# TangPrimer_base.net
KiCad netlist of a schematic drawn in EAGLE
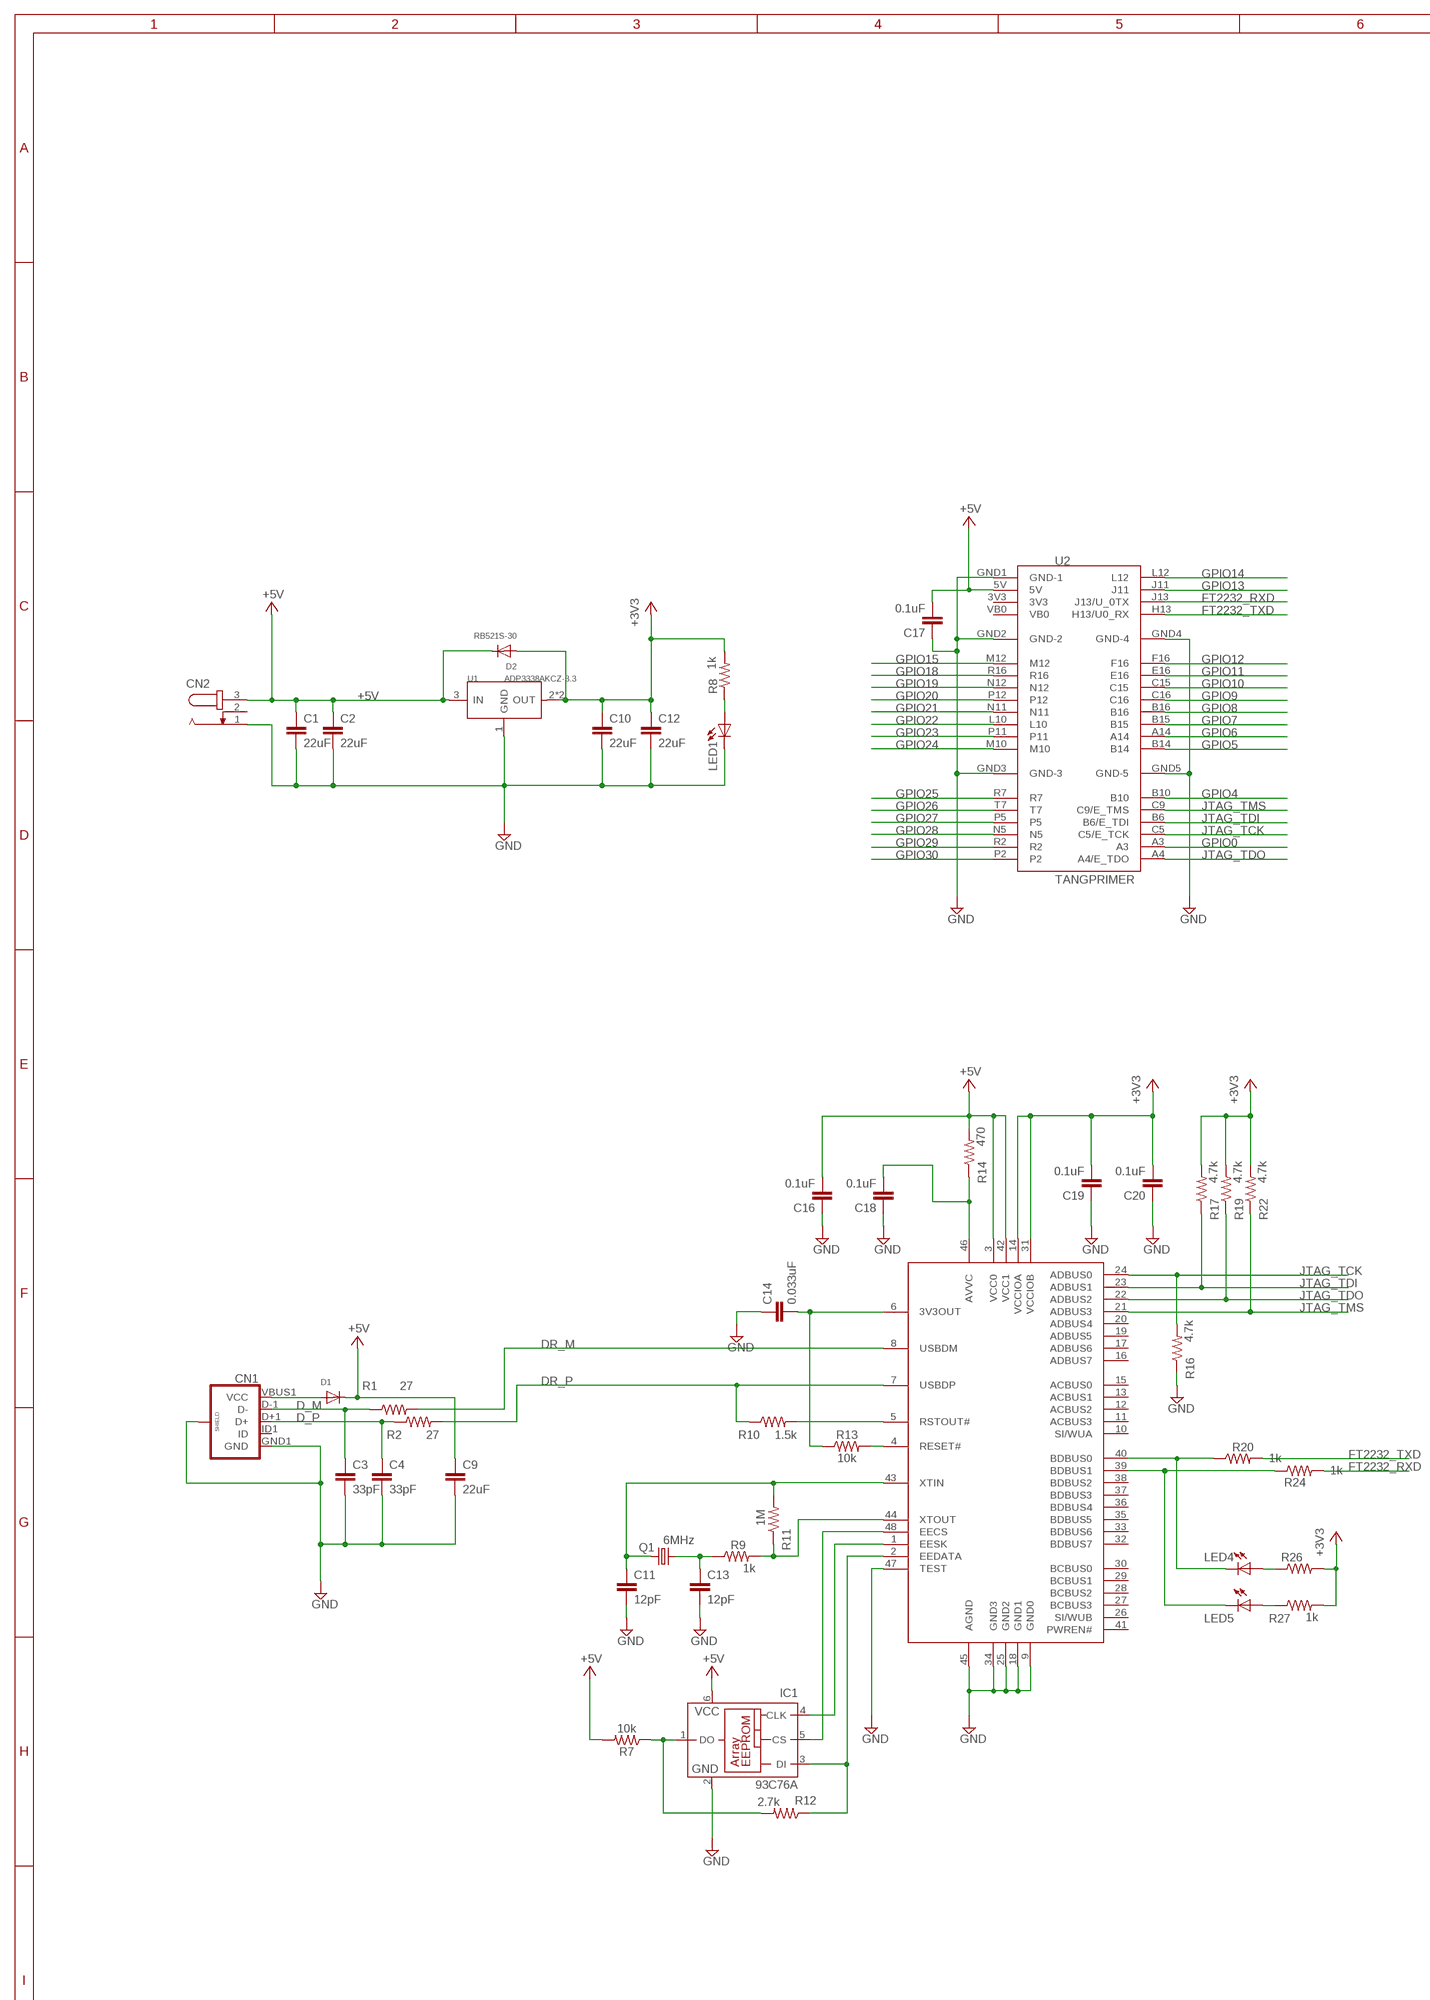
[diagram p0: schematic, sheet 1, part 1 of 2]
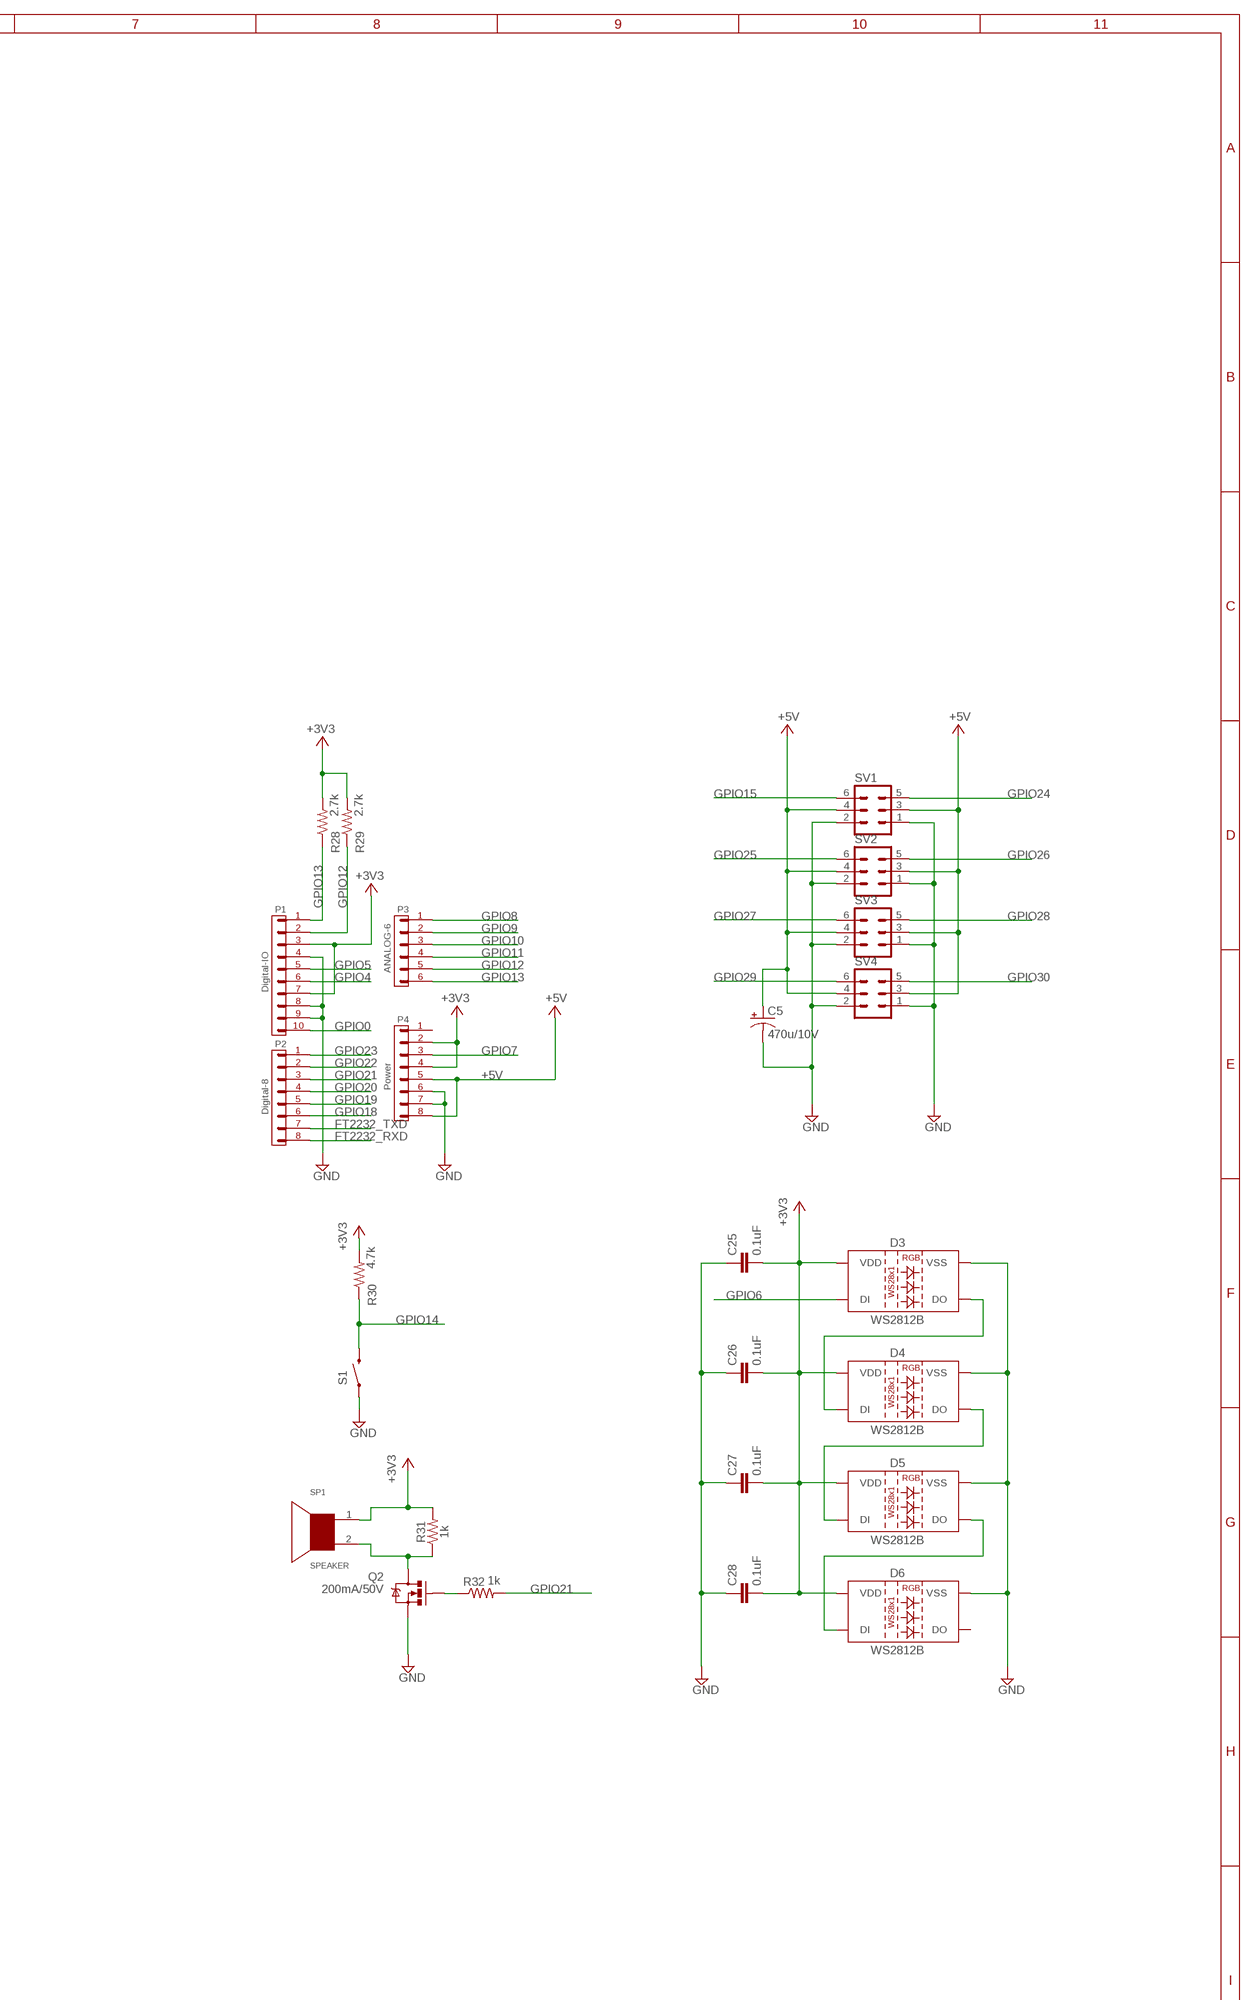
[diagram p1: schematic, sheet 1, part 2 of 2]

(export (version "E")
  (design (tool "Eeschema 10.0.6"))
  (components
    (comp (ref "C1")
      (value "22uF")
      (footprint "eagle-import:0603")
      (libsource (lib "eagle-import") (part "10UF-0603-6.3V-20%"))
    )
    (comp (ref "C2")
      (value "22uF")
      (footprint "eagle-import:0603")
      (libsource (lib "eagle-import") (part "10UF-0603-6.3V-20%"))
    )
    (comp (ref "C3")
      (value "33pF")
      (footprint "eagle-import:0603")
      (libsource (lib "eagle-import") (part "47PF-0603-50V-5%"))
    )
    (comp (ref "C4")
      (value "33pF")
      (footprint "eagle-import:0603")
      (libsource (lib "eagle-import") (part "47PF-0603-50V-5%"))
    )
    (comp (ref "C5")
      (value "470u/10V")
      (footprint "eagle-import:E2,5-7")
      (libsource (lib "eagle-import") (part "CPOL-USE2.5-7"))
    )
    (comp (ref "C9")
      (value "22uF")
      (footprint "eagle-import:0603")
      (libsource (lib "eagle-import") (part "10UF-0603-6.3V-20%"))
    )
    (comp (ref "C10")
      (value "22uF")
      (footprint "eagle-import:0603")
      (libsource (lib "eagle-import") (part "10UF-0603-6.3V-20%"))
    )
    (comp (ref "C11")
      (value "12pF")
      (footprint "eagle-import:0603")
      (libsource (lib "eagle-import") (part "47PF-0603-50V-5%"))
    )
    (comp (ref "C12")
      (value "22uF")
      (footprint "eagle-import:0603")
      (libsource (lib "eagle-import") (part "10UF-0603-6.3V-20%"))
    )
    (comp (ref "C13")
      (value "12pF")
      (footprint "eagle-import:0603")
      (libsource (lib "eagle-import") (part "47PF-0603-50V-5%"))
    )
    (comp (ref "C14")
      (value "0.033uF")
      (footprint "eagle-import:0603")
      (libsource (lib "eagle-import") (part "47PF-0603-50V-5%"))
    )
    (comp (ref "C16")
      (value "0.1uF")
      (footprint "eagle-import:0603")
      (libsource (lib "eagle-import") (part "0.1UF-0603-25V-5%"))
    )
    (comp (ref "C17")
      (value "0.1uF")
      (footprint "eagle-import:0603")
      (libsource (lib "eagle-import") (part "0.1UF-0603-25V-5%"))
    )
    (comp (ref "C18")
      (value "0.1uF")
      (footprint "eagle-import:0603")
      (libsource (lib "eagle-import") (part "0.1UF-0603-25V-5%"))
    )
    (comp (ref "C19")
      (value "0.1uF")
      (footprint "eagle-import:0603")
      (libsource (lib "eagle-import") (part "0.1UF-0603-25V-5%"))
    )
    (comp (ref "C20")
      (value "0.1uF")
      (footprint "eagle-import:0603")
      (libsource (lib "eagle-import") (part "0.1UF-0603-25V-5%"))
    )
    (comp (ref "C25")
      (value "0.1uF")
      (footprint "eagle-import:0603")
      (libsource (lib "eagle-import") (part "0.1UF-0603-25V-5%"))
    )
    (comp (ref "C26")
      (value "0.1uF")
      (footprint "eagle-import:0603")
      (libsource (lib "eagle-import") (part "0.1UF-0603-25V-5%"))
    )
    (comp (ref "C27")
      (value "0.1uF")
      (footprint "eagle-import:0603")
      (libsource (lib "eagle-import") (part "0.1UF-0603-25V-5%"))
    )
    (comp (ref "C28")
      (value "0.1uF")
      (footprint "eagle-import:0603")
      (libsource (lib "eagle-import") (part "0.1UF-0603-25V-5%"))
    )
    (comp (ref "CN1")
      (value "MCUBF-09")
      (footprint "eagle-import:MCUBF-09")
      (libsource (lib "eagle-import") (part "MCUBF-09"))
    )
    (comp (ref "CN2")
      (value "JACK-PLUG0")
      (footprint "eagle-import:SPC4077")
      (libsource (lib "eagle-import") (part "JACK-PLUG0"))
    )
    (comp (ref "D1")
      (value "DIODE_SOD-123FL")
      (footprint "eagle-import:SOD-123FL")
      (libsource (lib "eagle-import") (part "DIODE_SOD-123FL"))
    )
    (comp (ref "D2")
      (value "RB521S-30")
      (footprint "eagle-import:SOD-523")
      (libsource (lib "eagle-import") (part "DIODESOD-523"))
    )
    (comp (ref "D3")
      (value "WS2812B")
      (footprint "eagle-import:WS2812_2020")
      (libsource (lib "eagle-import") (part "WS2812_2020"))
    )
    (comp (ref "D4")
      (value "WS2812B")
      (footprint "eagle-import:WS2812_2020")
      (libsource (lib "eagle-import") (part "WS2812_2020"))
    )
    (comp (ref "D5")
      (value "WS2812B")
      (footprint "eagle-import:WS2812_2020")
      (libsource (lib "eagle-import") (part "WS2812_2020"))
    )
    (comp (ref "D6")
      (value "WS2812B")
      (footprint "eagle-import:WS2812_2020")
      (libsource (lib "eagle-import") (part "WS2812_2020"))
    )
    (comp (ref "IC1")
      (value "93C76A")
      (footprint "eagle-import:SOT23-6")
      (libsource (lib "eagle-import") (part "9376?AC"))
    )
    (comp (ref "IC2")
      (value "FT2232L")
      (footprint "eagle-import:LQFP48")
      (libsource (lib "eagle-import") (part "FT2232L"))
    )
    (comp (ref "LED1")
      (value "LEDCHIP-LED0805")
      (footprint "eagle-import:CHIP-LED0805")
      (libsource (lib "eagle-import") (part "LEDCHIP-LED0805"))
    )
    (comp (ref "LED4")
      (value "LEDCHIP-LED0805")
      (footprint "eagle-import:CHIP-LED0805")
      (libsource (lib "eagle-import") (part "LEDCHIP-LED0805"))
    )
    (comp (ref "LED5")
      (value "LEDCHIP-LED0805")
      (footprint "eagle-import:CHIP-LED0805")
      (libsource (lib "eagle-import") (part "LEDCHIP-LED0805"))
    )
    (comp (ref "Q1")
      (value "6MHz")
      (footprint "eagle-import:SM49")
      (libsource (lib "eagle-import") (part "CRYSTALSM49"))
    )
    (comp (ref "Q2")
      (value "200mA/50V")
      (footprint "eagle-import:SOT23-3")
      (libsource (lib "eagle-import") (part "MOSFET-NCHANNELBSS138"))
    )
    (comp (ref "R1")
      (value "27")
      (footprint "eagle-import:0603")
      (libsource (lib "eagle-import") (part "RESISTOR0603"))
    )
    (comp (ref "R2")
      (value "27")
      (footprint "eagle-import:0603")
      (libsource (lib "eagle-import") (part "RESISTOR0603"))
    )
    (comp (ref "R7")
      (value "10k")
      (footprint "eagle-import:0603")
      (libsource (lib "eagle-import") (part "RESISTOR0603"))
    )
    (comp (ref "R8")
      (value "1k")
      (footprint "eagle-import:0603")
      (libsource (lib "eagle-import") (part "RESISTOR0603"))
    )
    (comp (ref "R9")
      (value "1k")
      (footprint "eagle-import:0603")
      (libsource (lib "eagle-import") (part "RESISTOR0603"))
    )
    (comp (ref "R10")
      (value "1.5k")
      (footprint "eagle-import:0603")
      (libsource (lib "eagle-import") (part "RESISTOR0603"))
    )
    (comp (ref "R11")
      (value "1M")
      (footprint "eagle-import:0603")
      (libsource (lib "eagle-import") (part "RESISTOR0603"))
    )
    (comp (ref "R12")
      (value "2.7k")
      (footprint "eagle-import:0603")
      (libsource (lib "eagle-import") (part "RESISTOR0603"))
    )
    (comp (ref "R13")
      (value "10k")
      (footprint "eagle-import:0603")
      (libsource (lib "eagle-import") (part "RESISTOR0603"))
    )
    (comp (ref "R14")
      (value "470")
      (footprint "eagle-import:0603")
      (libsource (lib "eagle-import") (part "RESISTOR0603"))
    )
    (comp (ref "R16")
      (value "4.7k")
      (footprint "eagle-import:0603")
      (libsource (lib "eagle-import") (part "RESISTOR0603"))
    )
    (comp (ref "R17")
      (value "4.7k")
      (footprint "eagle-import:0603")
      (libsource (lib "eagle-import") (part "RESISTOR0603"))
    )
    (comp (ref "R19")
      (value "4.7k")
      (footprint "eagle-import:0603")
      (libsource (lib "eagle-import") (part "RESISTOR0603"))
    )
    (comp (ref "R20")
      (value "1k")
      (footprint "eagle-import:0603")
      (libsource (lib "eagle-import") (part "RESISTOR0603"))
    )
    (comp (ref "R22")
      (value "4.7k")
      (footprint "eagle-import:0603")
      (libsource (lib "eagle-import") (part "RESISTOR0603"))
    )
    (comp (ref "R24")
      (value "1k")
      (footprint "eagle-import:0603")
      (libsource (lib "eagle-import") (part "RESISTOR0603"))
    )
    (comp (ref "R26")
      (value "1k")
      (footprint "eagle-import:0603")
      (libsource (lib "eagle-import") (part "RESISTOR0603"))
    )
    (comp (ref "R27")
      (value "1k")
      (footprint "eagle-import:0603")
      (libsource (lib "eagle-import") (part "RESISTOR0603"))
    )
    (comp (ref "R28")
      (value "2.7k")
      (footprint "eagle-import:0603")
      (libsource (lib "eagle-import") (part "RESISTOR0603"))
    )
    (comp (ref "R29")
      (value "2.7k")
      (footprint "eagle-import:0603")
      (libsource (lib "eagle-import") (part "RESISTOR0603"))
    )
    (comp (ref "R30")
      (value "4.7k")
      (footprint "eagle-import:0603")
      (libsource (lib "eagle-import") (part "RESISTOR0603"))
    )
    (comp (ref "R31")
      (value "1k")
      (footprint "eagle-import:0603")
      (libsource (lib "eagle-import") (part "RESISTOR0603"))
    )
    (comp (ref "R32")
      (value "1k")
      (footprint "eagle-import:0603")
      (libsource (lib "eagle-import") (part "RESISTOR0603"))
    )
    (comp (ref "S1")
      (value "SWITCH-MOMENTARY-2SMD-1101NE")
      (footprint "eagle-import:TACTILE-SWITCH-1101NE")
      (libsource (lib "eagle-import") (part "SWITCH-MOMENTARY-2SMD-1101NE"))
    )
    (comp (ref "S2")
      (value "TANGPRIMER_BASE")
      (footprint "eagle-import:TANGPRIMER_BASE")
      (libsource (lib "eagle-import") (part "TANGPRIMER_BASE"))
    )
    (comp (ref "SP1")
      (value "SPEAKER")
      (footprint "eagle-import:SPEAKER")
      (libsource (lib "eagle-import") (part "SPEAKER"))
    )
    (comp (ref "SV1")
      (value "MA03-2")
      (footprint "eagle-import:MA03-2")
      (libsource (lib "eagle-import") (part "MA03-2"))
    )
    (comp (ref "SV2")
      (value "MA03-2")
      (footprint "eagle-import:MA03-2")
      (libsource (lib "eagle-import") (part "MA03-2"))
    )
    (comp (ref "SV3")
      (value "MA03-2")
      (footprint "eagle-import:MA03-2")
      (libsource (lib "eagle-import") (part "MA03-2"))
    )
    (comp (ref "SV4")
      (value "MA03-2")
      (footprint "eagle-import:MA03-2")
      (libsource (lib "eagle-import") (part "MA03-2"))
    )
    (comp (ref "U1")
      (value "ADP3338AKCZ-3.3")
      (footprint "eagle-import:SOT-223")
      (fields (field (name "MPN") "CJT1117-3.3"))
      (libsource (lib "eagle-import") (part "PMIC-CJT1117-3.3(SOT223)"))
    )
    (comp (ref "U2")
      (value "TANGPRIMER")
      (footprint "eagle-import:TANGPRIMER")
      (libsource (lib "eagle-import") (part "TANGPRIMER"))
    )
  )
  (nets
    (net (code "1") (name "+3V3") (class "Default")
      (node (ref "C10") (pin "1") (pinfunction "1_1") (pintype "passive"))
      (node (ref "C12") (pin "1") (pinfunction "1_1") (pintype "passive"))
      (node (ref "C19") (pin "2") (pinfunction "2_2") (pintype "passive"))
      (node (ref "C20") (pin "2") (pinfunction "2_2") (pintype "passive"))
      (node (ref "C25") (pin "2") (pinfunction "2_2") (pintype "passive"))
      (node (ref "C26") (pin "2") (pinfunction "2_2") (pintype "passive"))
      (node (ref "C27") (pin "2") (pinfunction "2_2") (pintype "passive"))
      (node (ref "C28") (pin "2") (pinfunction "2_2") (pintype "passive"))
      (node (ref "D2") (pin "A") (pinfunction "A_A") (pintype "passive"))
      (node (ref "D3") (pin "4") (pinfunction "VDD_4") (pintype "bidirectional"))
      (node (ref "D4") (pin "4") (pinfunction "VDD_4") (pintype "bidirectional"))
      (node (ref "D5") (pin "4") (pinfunction "VDD_4") (pintype "bidirectional"))
      (node (ref "D6") (pin "4") (pinfunction "VDD_4") (pintype "bidirectional"))
      (node (ref "IC2") (pin "14") (pinfunction "VCCIOA_14") (pintype "bidirectional"))
      (node (ref "IC2") (pin "31") (pinfunction "VCCIOB_31") (pintype "bidirectional"))
      (node (ref "R17") (pin "2") (pinfunction "2_2") (pintype "passive"))
      (node (ref "R19") (pin "2") (pinfunction "2_2") (pintype "passive"))
      (node (ref "R22") (pin "2") (pinfunction "2_2") (pintype "passive"))
      (node (ref "R26") (pin "2") (pinfunction "2_2") (pintype "passive"))
      (node (ref "R27") (pin "2") (pinfunction "2_2") (pintype "passive"))
      (node (ref "R28") (pin "2") (pinfunction "2_2") (pintype "passive"))
      (node (ref "R29") (pin "2") (pinfunction "2_2") (pintype "passive"))
      (node (ref "R30") (pin "2") (pinfunction "2_2") (pintype "passive"))
      (node (ref "R31") (pin "2") (pinfunction "2_2") (pintype "passive"))
      (node (ref "R8") (pin "2") (pinfunction "2_2") (pintype "passive"))
      (node (ref "S2") (pin "3V3-1") (pinfunction "3V3-1_3V3-1") (pintype "bidirectional"))
      (node (ref "S2") (pin "3V3-2") (pinfunction "3V3-2_3V3-2") (pintype "bidirectional"))
      (node (ref "S2") (pin "AREF") (pinfunction "AREF_AREF") (pintype "bidirectional"))
      (node (ref "S2") (pin "D11") (pinfunction "D11_D11") (pintype "bidirectional"))
      (node (ref "SP1") (pin "1") (pinfunction "1_1") (pintype "bidirectional"))
      (node (ref "U1") (pin "2") (pinfunction "OUT_2") (pintype "bidirectional"))
      (node (ref "U1") (pin "TER") (pinfunction "OUT_TER") (pintype "bidirectional"))
    )
    (net (code "2") (name "+5V") (class "Default")
      (node (ref "C1") (pin "1") (pinfunction "1_1") (pintype "passive"))
      (node (ref "C16") (pin "2") (pinfunction "2_2") (pintype "passive"))
      (node (ref "C17") (pin "2") (pinfunction "2_2") (pintype "passive"))
      (node (ref "C2") (pin "1") (pinfunction "1_1") (pintype "passive"))
      (node (ref "C5") (pin "+") (pinfunction "+_+") (pintype "passive"))
      (node (ref "C9") (pin "1") (pinfunction "1_1") (pintype "passive"))
      (node (ref "CN2") (pin "3") (pinfunction "3_3") (pintype "passive"))
      (node (ref "D1") (pin "C") (pinfunction "C_C") (pintype "passive"))
      (node (ref "D2") (pin "K") (pinfunction "C_K") (pintype "passive"))
      (node (ref "IC1") (pin "6") (pinfunction "VCC_6") (pintype "power_in"))
      (node (ref "IC2") (pin "3") (pinfunction "VCC0_3") (pintype "bidirectional"))
      (node (ref "IC2") (pin "42") (pinfunction "VCC1_42") (pintype "bidirectional"))
      (node (ref "R14") (pin "2") (pinfunction "2_2") (pintype "passive"))
      (node (ref "R7") (pin "2") (pinfunction "2_2") (pintype "passive"))
      (node (ref "S2") (pin "5V") (pinfunction "5V_5V") (pintype "bidirectional"))
      (node (ref "S2") (pin "VIN") (pinfunction "VIN_VIN") (pintype "bidirectional"))
      (node (ref "SV1") (pin "3") (pinfunction "3_3") (pintype "passive"))
      (node (ref "SV1") (pin "4") (pinfunction "4_4") (pintype "passive"))
      (node (ref "SV2") (pin "3") (pinfunction "3_3") (pintype "passive"))
      (node (ref "SV2") (pin "4") (pinfunction "4_4") (pintype "passive"))
      (node (ref "SV3") (pin "3") (pinfunction "3_3") (pintype "passive"))
      (node (ref "SV3") (pin "4") (pinfunction "4_4") (pintype "passive"))
      (node (ref "SV4") (pin "3") (pinfunction "3_3") (pintype "passive"))
      (node (ref "SV4") (pin "4") (pinfunction "4_4") (pintype "passive"))
      (node (ref "U1") (pin "3") (pinfunction "IN_3") (pintype "bidirectional"))
      (node (ref "U2") (pin "5V") (pinfunction "5V_5V") (pintype "passive"))
    )
    (net (code "3") (name "/DR_M") (class "Default")
      (node (ref "IC2") (pin "8") (pinfunction "USBDM_8") (pintype "bidirectional"))
      (node (ref "R1") (pin "2") (pinfunction "2_2") (pintype "passive"))
    )
    (net (code "4") (name "/DR_P") (class "Default")
      (node (ref "IC2") (pin "7") (pinfunction "USBDP_7") (pintype "bidirectional"))
      (node (ref "R10") (pin "1") (pinfunction "1_1") (pintype "passive"))
      (node (ref "R2") (pin "2") (pinfunction "2_2") (pintype "passive"))
    )
    (net (code "5") (name "/D_M") (class "Default")
      (node (ref "C3") (pin "1") (pinfunction "1_1") (pintype "passive"))
      (node (ref "CN1") (pin "D-1") (pinfunction "D-_D-1") (pintype "bidirectional"))
      (node (ref "R1") (pin "1") (pinfunction "1_1") (pintype "passive"))
    )
    (net (code "6") (name "/D_P") (class "Default")
      (node (ref "C4") (pin "1") (pinfunction "1_1") (pintype "passive"))
      (node (ref "CN1") (pin "D+1") (pinfunction "D+_D+1") (pintype "bidirectional"))
      (node (ref "R2") (pin "1") (pinfunction "1_1") (pintype "passive"))
    )
    (net (code "7") (name "/FT2232_RXD") (class "Default")
      (node (ref "R24") (pin "2") (pinfunction "2_2") (pintype "passive"))
      (node (ref "S2") (pin "RXD") (pinfunction "RX_RXD") (pintype "bidirectional"))
      (node (ref "U2") (pin "J13") (pinfunction "J13/U_0TX_J13") (pintype "passive"))
    )
    (net (code "8") (name "/FT2232_TXD") (class "Default")
      (node (ref "R20") (pin "2") (pinfunction "2_2") (pintype "passive"))
      (node (ref "S2") (pin "TXD") (pinfunction "TX_TXD") (pintype "bidirectional"))
      (node (ref "U2") (pin "H13") (pinfunction "H13/U0_RX_H13") (pintype "passive"))
    )
    (net (code "9") (name "/GPIO0") (class "Default")
      (node (ref "S2") (pin "D8") (pinfunction "D8_D8") (pintype "bidirectional"))
      (node (ref "U2") (pin "A3") (pinfunction "A3_A3") (pintype "passive"))
    )
    (net (code "10") (name "/GPIO4") (class "Default")
      (node (ref "S2") (pin "D12") (pinfunction "D12_D12") (pintype "bidirectional"))
      (node (ref "U2") (pin "B10") (pinfunction "B10_B10") (pintype "passive"))
    )
    (net (code "11") (name "/GPIO5") (class "Default")
      (node (ref "S2") (pin "D13") (pinfunction "D13_D13") (pintype "bidirectional"))
      (node (ref "U2") (pin "B14") (pinfunction "B14_B14") (pintype "passive"))
    )
    (net (code "12") (name "/GPIO6") (class "Default")
      (node (ref "D3") (pin "3") (pinfunction "DI_3") (pintype "bidirectional"))
      (node (ref "U2") (pin "A14") (pinfunction "A14_A14") (pintype "passive"))
    )
    (net (code "13") (name "/GPIO7") (class "Default")
      (node (ref "S2") (pin "RESET") (pinfunction "RESET_RESET") (pintype "bidirectional"))
      (node (ref "U2") (pin "B15") (pinfunction "B15_B15") (pintype "passive"))
    )
    (net (code "14") (name "/GPIO8") (class "Default")
      (node (ref "S2") (pin "A0") (pinfunction "A0_A0") (pintype "bidirectional"))
      (node (ref "U2") (pin "B16") (pinfunction "B16_B16") (pintype "passive"))
    )
    (net (code "15") (name "/GPIO9") (class "Default")
      (node (ref "S2") (pin "A1") (pinfunction "A1_A1") (pintype "bidirectional"))
      (node (ref "U2") (pin "C16") (pinfunction "C16_C16") (pintype "passive"))
    )
    (net (code "16") (name "/GPIO10") (class "Default")
      (node (ref "S2") (pin "A2") (pinfunction "A2_A2") (pintype "bidirectional"))
      (node (ref "U2") (pin "C15") (pinfunction "C15_C15") (pintype "passive"))
    )
    (net (code "17") (name "/GPIO11") (class "Default")
      (node (ref "S2") (pin "A3") (pinfunction "A3_A3") (pintype "bidirectional"))
      (node (ref "U2") (pin "E16") (pinfunction "E16_E16") (pintype "passive"))
    )
    (net (code "18") (name "/GPIO12") (class "Default")
      (node (ref "R29") (pin "1") (pinfunction "1_1") (pintype "passive"))
      (node (ref "S2") (pin "A4") (pinfunction "A4_A4") (pintype "bidirectional"))
      (node (ref "S2") (pin "SDA") (pinfunction "SDA_SDA") (pintype "bidirectional"))
      (node (ref "U2") (pin "F16") (pinfunction "F16_F16") (pintype "passive"))
    )
    (net (code "19") (name "/GPIO13") (class "Default")
      (node (ref "R28") (pin "1") (pinfunction "1_1") (pintype "passive"))
      (node (ref "S2") (pin "A5") (pinfunction "A5_A5") (pintype "bidirectional"))
      (node (ref "S2") (pin "SCL") (pinfunction "SCL_SCL") (pintype "bidirectional"))
      (node (ref "U2") (pin "J11") (pinfunction "J11_J11") (pintype "passive"))
    )
    (net (code "20") (name "/GPIO14") (class "Default")
      (node (ref "R30") (pin "1") (pinfunction "1_1") (pintype "passive"))
      (node (ref "S1") (pin "2") (pinfunction "2_2") (pintype "passive"))
      (node (ref "U2") (pin "L12") (pinfunction "L12_L12") (pintype "passive"))
    )
    (net (code "21") (name "/GPIO15") (class "Default")
      (node (ref "SV1") (pin "6") (pinfunction "6_6") (pintype "passive"))
      (node (ref "U2") (pin "M12") (pinfunction "M12_M12") (pintype "passive"))
    )
    (net (code "22") (name "/GPIO18") (class "Default")
      (node (ref "S2") (pin "D2") (pinfunction "D2_D2") (pintype "bidirectional"))
      (node (ref "U2") (pin "R16") (pinfunction "R16_R16") (pintype "passive"))
    )
    (net (code "23") (name "/GPIO19") (class "Default")
      (node (ref "S2") (pin "D3") (pinfunction "D3_D3") (pintype "bidirectional"))
      (node (ref "U2") (pin "N12") (pinfunction "N12_N12") (pintype "passive"))
    )
    (net (code "24") (name "/GPIO20") (class "Default")
      (node (ref "S2") (pin "D4") (pinfunction "D4_D4") (pintype "bidirectional"))
      (node (ref "U2") (pin "P12") (pinfunction "P12_P12") (pintype "passive"))
    )
    (net (code "25") (name "/GPIO21") (class "Default")
      (node (ref "R32") (pin "2") (pinfunction "2_2") (pintype "passive"))
      (node (ref "S2") (pin "D5") (pinfunction "D5_D5") (pintype "bidirectional"))
      (node (ref "U2") (pin "N11") (pinfunction "N11_N11") (pintype "passive"))
    )
    (net (code "26") (name "/GPIO22") (class "Default")
      (node (ref "S2") (pin "D6") (pinfunction "D6_D6") (pintype "bidirectional"))
      (node (ref "U2") (pin "L10") (pinfunction "L10_L10") (pintype "passive"))
    )
    (net (code "27") (name "/GPIO23") (class "Default")
      (node (ref "S2") (pin "D7") (pinfunction "D7_D7") (pintype "bidirectional"))
      (node (ref "U2") (pin "P11") (pinfunction "P11_P11") (pintype "passive"))
    )
    (net (code "28") (name "/GPIO24") (class "Default")
      (node (ref "SV1") (pin "5") (pinfunction "5_5") (pintype "passive"))
      (node (ref "U2") (pin "M10") (pinfunction "M10_M10") (pintype "passive"))
    )
    (net (code "29") (name "/GPIO25") (class "Default")
      (node (ref "SV2") (pin "6") (pinfunction "6_6") (pintype "passive"))
      (node (ref "U2") (pin "R7") (pinfunction "R7_R7") (pintype "passive"))
    )
    (net (code "30") (name "/GPIO26") (class "Default")
      (node (ref "SV2") (pin "5") (pinfunction "5_5") (pintype "passive"))
      (node (ref "U2") (pin "T7") (pinfunction "T7_T7") (pintype "passive"))
    )
    (net (code "31") (name "/GPIO27") (class "Default")
      (node (ref "SV3") (pin "6") (pinfunction "6_6") (pintype "passive"))
      (node (ref "U2") (pin "P5") (pinfunction "P5_P5") (pintype "passive"))
    )
    (net (code "32") (name "/GPIO28") (class "Default")
      (node (ref "SV3") (pin "5") (pinfunction "5_5") (pintype "passive"))
      (node (ref "U2") (pin "N5") (pinfunction "N5_N5") (pintype "passive"))
    )
    (net (code "33") (name "/GPIO29") (class "Default")
      (node (ref "SV4") (pin "6") (pinfunction "6_6") (pintype "passive"))
      (node (ref "U2") (pin "R2") (pinfunction "R2_R2") (pintype "passive"))
    )
    (net (code "34") (name "/GPIO30") (class "Default")
      (node (ref "SV4") (pin "5") (pinfunction "5_5") (pintype "passive"))
      (node (ref "U2") (pin "P2") (pinfunction "P2_P2") (pintype "passive"))
    )
    (net (code "35") (name "/JTAG_TCK") (class "Default")
      (node (ref "IC2") (pin "24") (pinfunction "ADBUS0_24") (pintype "bidirectional"))
      (node (ref "R16") (pin "2") (pinfunction "2_2") (pintype "passive"))
      (node (ref "U2") (pin "C5") (pinfunction "C5/E_TCK_C5") (pintype "passive"))
    )
    (net (code "36") (name "/JTAG_TDI") (class "Default")
      (node (ref "IC2") (pin "23") (pinfunction "ADBUS1_23") (pintype "bidirectional"))
      (node (ref "R17") (pin "1") (pinfunction "1_1") (pintype "passive"))
      (node (ref "U2") (pin "B6") (pinfunction "B6/E_TDI_B6") (pintype "passive"))
    )
    (net (code "37") (name "/JTAG_TDO") (class "Default")
      (node (ref "IC2") (pin "22") (pinfunction "ADBUS2_22") (pintype "bidirectional"))
      (node (ref "R19") (pin "1") (pinfunction "1_1") (pintype "passive"))
      (node (ref "U2") (pin "A4") (pinfunction "A4/E_TDO_A4") (pintype "passive"))
    )
    (net (code "38") (name "/JTAG_TMS") (class "Default")
      (node (ref "IC2") (pin "21") (pinfunction "ADBUS3_21") (pintype "bidirectional"))
      (node (ref "R22") (pin "1") (pinfunction "1_1") (pintype "passive"))
      (node (ref "U2") (pin "C9") (pinfunction "C9/E_TMS_C9") (pintype "passive"))
    )
    (net (code "39") (name "GND") (class "Default")
      (node (ref "C1") (pin "2") (pinfunction "2_2") (pintype "passive"))
      (node (ref "C10") (pin "2") (pinfunction "2_2") (pintype "passive"))
      (node (ref "C11") (pin "2") (pinfunction "2_2") (pintype "passive"))
      (node (ref "C12") (pin "2") (pinfunction "2_2") (pintype "passive"))
      (node (ref "C13") (pin "2") (pinfunction "2_2") (pintype "passive"))
      (node (ref "C14") (pin "1") (pinfunction "1_1") (pintype "passive"))
      (node (ref "C16") (pin "1") (pinfunction "1_1") (pintype "passive"))
      (node (ref "C17") (pin "1") (pinfunction "1_1") (pintype "passive"))
      (node (ref "C18") (pin "1") (pinfunction "1_1") (pintype "passive"))
      (node (ref "C19") (pin "1") (pinfunction "1_1") (pintype "passive"))
      (node (ref "C2") (pin "2") (pinfunction "2_2") (pintype "passive"))
      (node (ref "C20") (pin "1") (pinfunction "1_1") (pintype "passive"))
      (node (ref "C25") (pin "1") (pinfunction "1_1") (pintype "passive"))
      (node (ref "C26") (pin "1") (pinfunction "1_1") (pintype "passive"))
      (node (ref "C27") (pin "1") (pinfunction "1_1") (pintype "passive"))
      (node (ref "C28") (pin "1") (pinfunction "1_1") (pintype "passive"))
      (node (ref "C3") (pin "2") (pinfunction "2_2") (pintype "passive"))
      (node (ref "C4") (pin "2") (pinfunction "2_2") (pintype "passive"))
      (node (ref "C5") (pin "-") (pinfunction "-_-") (pintype "passive"))
      (node (ref "C9") (pin "2") (pinfunction "2_2") (pintype "passive"))
      (node (ref "CN1") (pin "GND1") (pinfunction "GND_GND1") (pintype "bidirectional"))
      (node (ref "CN1") (pin "GND@1") (pinfunction "SHIELD_GND@1") (pintype "bidirectional"))
      (node (ref "CN1") (pin "GND@2") (pinfunction "SHIELD_GND@2") (pintype "bidirectional"))
      (node (ref "CN1") (pin "GND@3") (pinfunction "SHIELD_GND@3") (pintype "bidirectional"))
      (node (ref "CN1") (pin "GND@4") (pinfunction "SHIELD_GND@4") (pintype "bidirectional"))
      (node (ref "CN1") (pin "GND@5") (pinfunction "SHIELD_GND@5") (pintype "bidirectional"))
      (node (ref "CN1") (pin "GND@6") (pinfunction "SHIELD_GND@6") (pintype "bidirectional"))
      (node (ref "CN1") (pin "GND@7") (pinfunction "SHIELD_GND@7") (pintype "bidirectional"))
      (node (ref "CN1") (pin "GND@8") (pinfunction "SHIELD_GND@8") (pintype "bidirectional"))
      (node (ref "CN2") (pin "1") (pinfunction "1_1") (pintype "passive"))
      (node (ref "D3") (pin "2") (pinfunction "VSS_2") (pintype "bidirectional"))
      (node (ref "D4") (pin "2") (pinfunction "VSS_2") (pintype "bidirectional"))
      (node (ref "D5") (pin "2") (pinfunction "VSS_2") (pintype "bidirectional"))
      (node (ref "D6") (pin "2") (pinfunction "VSS_2") (pintype "bidirectional"))
      (node (ref "IC1") (pin "2") (pinfunction "GND_2") (pintype "power_in"))
      (node (ref "IC2") (pin "18") (pinfunction "GND1_18") (pintype "bidirectional"))
      (node (ref "IC2") (pin "25") (pinfunction "GND2_25") (pintype "bidirectional"))
      (node (ref "IC2") (pin "34") (pinfunction "GND3_34") (pintype "bidirectional"))
      (node (ref "IC2") (pin "45") (pinfunction "AGND_45") (pintype "bidirectional"))
      (node (ref "IC2") (pin "47") (pinfunction "TEST_47") (pintype "bidirectional"))
      (node (ref "IC2") (pin "9") (pinfunction "GND0_9") (pintype "bidirectional"))
      (node (ref "LED1") (pin "C") (pinfunction "C_C") (pintype "passive"))
      (node (ref "Q2") (pin "2") (pinfunction "S_2") (pintype "passive"))
      (node (ref "R16") (pin "1") (pinfunction "1_1") (pintype "passive"))
      (node (ref "S1") (pin "1") (pinfunction "1_1") (pintype "passive"))
      (node (ref "S2") (pin "D10") (pinfunction "D10_D10") (pintype "bidirectional"))
      (node (ref "S2") (pin "D9") (pinfunction "D9_D9") (pintype "bidirectional"))
      (node (ref "S2") (pin "GND-1") (pinfunction "GND1_GND-1") (pintype "bidirectional"))
      (node (ref "S2") (pin "GND-2") (pinfunction "GND2_GND-2") (pintype "bidirectional"))
      (node (ref "S2") (pin "GND-3") (pinfunction "GND3_GND-3") (pintype "bidirectional"))
      (node (ref "SV1") (pin "1") (pinfunction "1_1") (pintype "passive"))
      (node (ref "SV1") (pin "2") (pinfunction "2_2") (pintype "passive"))
      (node (ref "SV2") (pin "1") (pinfunction "1_1") (pintype "passive"))
      (node (ref "SV2") (pin "2") (pinfunction "2_2") (pintype "passive"))
      (node (ref "SV3") (pin "1") (pinfunction "1_1") (pintype "passive"))
      (node (ref "SV3") (pin "2") (pinfunction "2_2") (pintype "passive"))
      (node (ref "SV4") (pin "1") (pinfunction "1_1") (pintype "passive"))
      (node (ref "SV4") (pin "2") (pinfunction "2_2") (pintype "passive"))
      (node (ref "U1") (pin "1") (pinfunction "GND_1") (pintype "bidirectional"))
      (node (ref "U2") (pin "GND1") (pinfunction "GND-1_GND1") (pintype "passive"))
      (node (ref "U2") (pin "GND2") (pinfunction "GND-2_GND2") (pintype "passive"))
      (node (ref "U2") (pin "GND3") (pinfunction "GND-3_GND3") (pintype "passive"))
      (node (ref "U2") (pin "GND4") (pinfunction "GND-4_GND4") (pintype "passive"))
      (node (ref "U2") (pin "GND5") (pinfunction "GND-5_GND5") (pintype "passive"))
    )
    (net (code "40") (name "Net-(C13-Pad1)") (class "Default")
      (node (ref "C13") (pin "1") (pinfunction "1_1") (pintype "passive"))
      (node (ref "Q1") (pin "2") (pinfunction "2_2") (pintype "passive"))
      (node (ref "R9") (pin "1") (pinfunction "1_1") (pintype "passive"))
    )
    (net (code "41") (name "Net-(CN1-VCC)") (class "Default")
      (node (ref "CN1") (pin "VBUS1") (pinfunction "VCC_VBUS1") (pintype "bidirectional"))
      (node (ref "D1") (pin "A") (pinfunction "A_A") (pintype "passive"))
    )
    (net (code "42") (name "Net-(D3-DO)") (class "Default")
      (node (ref "D3") (pin "1") (pinfunction "DO_1") (pintype "bidirectional"))
      (node (ref "D4") (pin "3") (pinfunction "DI_3") (pintype "bidirectional"))
    )
    (net (code "43") (name "Net-(D4-DO)") (class "Default")
      (node (ref "D4") (pin "1") (pinfunction "DO_1") (pintype "bidirectional"))
      (node (ref "D5") (pin "3") (pinfunction "DI_3") (pintype "bidirectional"))
    )
    (net (code "44") (name "Net-(D5-DO)") (class "Default")
      (node (ref "D5") (pin "1") (pinfunction "DO_1") (pintype "bidirectional"))
      (node (ref "D6") (pin "3") (pinfunction "DI_3") (pintype "bidirectional"))
    )
    (net (code "45") (name "Net-(IC1-CLK)") (class "Default")
      (node (ref "IC1") (pin "4") (pinfunction "CLK_4") (pintype "input"))
      (node (ref "IC2") (pin "1") (pinfunction "EESK_1") (pintype "bidirectional"))
    )
    (net (code "46") (name "Net-(IC1-CS)") (class "Default")
      (node (ref "IC1") (pin "5") (pinfunction "CS_5") (pintype "input"))
      (node (ref "IC2") (pin "48") (pinfunction "EECS_48") (pintype "bidirectional"))
    )
    (net (code "47") (name "Net-(IC1-DI)") (class "Default")
      (node (ref "IC1") (pin "3") (pinfunction "DI_3") (pintype "input"))
      (node (ref "IC2") (pin "2") (pinfunction "EEDATA_2") (pintype "bidirectional"))
      (node (ref "R12") (pin "1") (pinfunction "1_1") (pintype "passive"))
    )
    (net (code "48") (name "Net-(IC1-DO)") (class "Default")
      (node (ref "IC1") (pin "1") (pinfunction "DO_1") (pintype "tri_state"))
      (node (ref "R12") (pin "2") (pinfunction "2_2") (pintype "passive"))
      (node (ref "R7") (pin "1") (pinfunction "1_1") (pintype "passive"))
    )
    (net (code "49") (name "Net-(IC2-3V3OUT)") (class "Default")
      (node (ref "C14") (pin "2") (pinfunction "2_2") (pintype "passive"))
      (node (ref "IC2") (pin "6") (pinfunction "3V3OUT_6") (pintype "bidirectional"))
      (node (ref "R13") (pin "1") (pinfunction "1_1") (pintype "passive"))
    )
    (net (code "50") (name "Net-(IC2-AVVC)") (class "Default")
      (node (ref "C18") (pin "2") (pinfunction "2_2") (pintype "passive"))
      (node (ref "IC2") (pin "46") (pinfunction "AVVC_46") (pintype "bidirectional"))
      (node (ref "R14") (pin "1") (pinfunction "1_1") (pintype "passive"))
    )
    (net (code "51") (name "Net-(IC2-BDBUS0)") (class "Default")
      (node (ref "IC2") (pin "40") (pinfunction "BDBUS0_40") (pintype "bidirectional"))
      (node (ref "LED4") (pin "C") (pinfunction "C_C") (pintype "passive"))
      (node (ref "R20") (pin "1") (pinfunction "1_1") (pintype "passive"))
    )
    (net (code "52") (name "Net-(IC2-BDBUS1)") (class "Default")
      (node (ref "IC2") (pin "39") (pinfunction "BDBUS1_39") (pintype "bidirectional"))
      (node (ref "LED5") (pin "C") (pinfunction "C_C") (pintype "passive"))
      (node (ref "R24") (pin "1") (pinfunction "1_1") (pintype "passive"))
    )
    (net (code "53") (name "Net-(IC2-RESET#)") (class "Default")
      (node (ref "IC2") (pin "4") (pinfunction "RESET#_4") (pintype "bidirectional"))
      (node (ref "R13") (pin "2") (pinfunction "2_2") (pintype "passive"))
    )
    (net (code "54") (name "Net-(IC2-RSTOUT#)") (class "Default")
      (node (ref "IC2") (pin "5") (pinfunction "RSTOUT#_5") (pintype "bidirectional"))
      (node (ref "R10") (pin "2") (pinfunction "2_2") (pintype "passive"))
    )
    (net (code "55") (name "Net-(IC2-XTIN)") (class "Default")
      (node (ref "C11") (pin "1") (pinfunction "1_1") (pintype "passive"))
      (node (ref "IC2") (pin "43") (pinfunction "XTIN_43") (pintype "bidirectional"))
      (node (ref "Q1") (pin "1") (pinfunction "1_1") (pintype "passive"))
      (node (ref "R11") (pin "2") (pinfunction "2_2") (pintype "passive"))
    )
    (net (code "56") (name "Net-(IC2-XTOUT)") (class "Default")
      (node (ref "IC2") (pin "44") (pinfunction "XTOUT_44") (pintype "bidirectional"))
      (node (ref "R11") (pin "1") (pinfunction "1_1") (pintype "passive"))
      (node (ref "R9") (pin "2") (pinfunction "2_2") (pintype "passive"))
    )
    (net (code "57") (name "Net-(LED1-PadA)") (class "Default")
      (node (ref "LED1") (pin "A") (pinfunction "A_A") (pintype "passive"))
      (node (ref "R8") (pin "1") (pinfunction "1_1") (pintype "passive"))
    )
    (net (code "58") (name "Net-(LED4-PadA)") (class "Default")
      (node (ref "LED4") (pin "A") (pinfunction "A_A") (pintype "passive"))
      (node (ref "R26") (pin "1") (pinfunction "1_1") (pintype "passive"))
    )
    (net (code "59") (name "Net-(LED5-PadA)") (class "Default")
      (node (ref "LED5") (pin "A") (pinfunction "A_A") (pintype "passive"))
      (node (ref "R27") (pin "1") (pinfunction "1_1") (pintype "passive"))
    )
    (net (code "60") (name "Net-(Q2-D)") (class "Default")
      (node (ref "Q2") (pin "3") (pinfunction "D_3") (pintype "passive"))
      (node (ref "R31") (pin "1") (pinfunction "1_1") (pintype "passive"))
      (node (ref "SP1") (pin "2") (pinfunction "2_2") (pintype "bidirectional"))
    )
    (net (code "61") (name "Net-(Q2-G)") (class "Default")
      (node (ref "Q2") (pin "1") (pinfunction "G_1") (pintype "passive"))
      (node (ref "R32") (pin "1") (pinfunction "1_1") (pintype "passive"))
    )
    (net (code "62") (name "unconnected-(CN1-ID-PadID1)") (class "Default")
      (node (ref "CN1") (pin "ID1") (pinfunction "ID_ID1") (pintype "bidirectional"))
    )
    (net (code "63") (name "unconnected-(CN2-Pad2)") (class "Default")
      (node (ref "CN2") (pin "2") (pinfunction "2_2") (pintype "passive"))
    )
    (net (code "64") (name "unconnected-(D6-DO-Pad1)") (class "Default")
      (node (ref "D6") (pin "1") (pinfunction "DO_1") (pintype "bidirectional"))
    )
    (net (code "65") (name "unconnected-(IC2-ACBUS0-Pad15)") (class "Default")
      (node (ref "IC2") (pin "15") (pinfunction "ACBUS0_15") (pintype "bidirectional"))
    )
    (net (code "66") (name "unconnected-(IC2-ACBUS1-Pad13)") (class "Default")
      (node (ref "IC2") (pin "13") (pinfunction "ACBUS1_13") (pintype "bidirectional"))
    )
    (net (code "67") (name "unconnected-(IC2-ACBUS2-Pad12)") (class "Default")
      (node (ref "IC2") (pin "12") (pinfunction "ACBUS2_12") (pintype "bidirectional"))
    )
    (net (code "68") (name "unconnected-(IC2-ACBUS3-Pad11)") (class "Default")
      (node (ref "IC2") (pin "11") (pinfunction "ACBUS3_11") (pintype "bidirectional"))
    )
    (net (code "69") (name "unconnected-(IC2-ADBUS4-Pad20)") (class "Default")
      (node (ref "IC2") (pin "20") (pinfunction "ADBUS4_20") (pintype "bidirectional"))
    )
    (net (code "70") (name "unconnected-(IC2-ADBUS5-Pad19)") (class "Default")
      (node (ref "IC2") (pin "19") (pinfunction "ADBUS5_19") (pintype "bidirectional"))
    )
    (net (code "71") (name "unconnected-(IC2-ADBUS6-Pad17)") (class "Default")
      (node (ref "IC2") (pin "17") (pinfunction "ADBUS6_17") (pintype "bidirectional"))
    )
    (net (code "72") (name "unconnected-(IC2-ADBUS7-Pad16)") (class "Default")
      (node (ref "IC2") (pin "16") (pinfunction "ADBUS7_16") (pintype "bidirectional"))
    )
    (net (code "73") (name "unconnected-(IC2-BCBUS0-Pad30)") (class "Default")
      (node (ref "IC2") (pin "30") (pinfunction "BCBUS0_30") (pintype "bidirectional"))
    )
    (net (code "74") (name "unconnected-(IC2-BCBUS1-Pad29)") (class "Default")
      (node (ref "IC2") (pin "29") (pinfunction "BCBUS1_29") (pintype "bidirectional"))
    )
    (net (code "75") (name "unconnected-(IC2-BCBUS2-Pad28)") (class "Default")
      (node (ref "IC2") (pin "28") (pinfunction "BCBUS2_28") (pintype "bidirectional"))
    )
    (net (code "76") (name "unconnected-(IC2-BCBUS3-Pad27)") (class "Default")
      (node (ref "IC2") (pin "27") (pinfunction "BCBUS3_27") (pintype "bidirectional"))
    )
    (net (code "77") (name "unconnected-(IC2-BDBUS2-Pad38)") (class "Default")
      (node (ref "IC2") (pin "38") (pinfunction "BDBUS2_38") (pintype "bidirectional"))
    )
    (net (code "78") (name "unconnected-(IC2-BDBUS3-Pad37)") (class "Default")
      (node (ref "IC2") (pin "37") (pinfunction "BDBUS3_37") (pintype "bidirectional"))
    )
    (net (code "79") (name "unconnected-(IC2-BDBUS4-Pad36)") (class "Default")
      (node (ref "IC2") (pin "36") (pinfunction "BDBUS4_36") (pintype "bidirectional"))
    )
    (net (code "80") (name "unconnected-(IC2-BDBUS5-Pad35)") (class "Default")
      (node (ref "IC2") (pin "35") (pinfunction "BDBUS5_35") (pintype "bidirectional"))
    )
    (net (code "81") (name "unconnected-(IC2-BDBUS6-Pad33)") (class "Default")
      (node (ref "IC2") (pin "33") (pinfunction "BDBUS6_33") (pintype "bidirectional"))
    )
    (net (code "82") (name "unconnected-(IC2-BDBUS7-Pad32)") (class "Default")
      (node (ref "IC2") (pin "32") (pinfunction "BDBUS7_32") (pintype "bidirectional"))
    )
    (net (code "83") (name "unconnected-(IC2-PWREN#-Pad41)") (class "Default")
      (node (ref "IC2") (pin "41") (pinfunction "PWREN#_41") (pintype "bidirectional"))
    )
    (net (code "84") (name "unconnected-(IC2-SI{slash}WUA-Pad10)") (class "Default")
      (node (ref "IC2") (pin "10") (pinfunction "SI/WUA_10") (pintype "bidirectional"))
    )
    (net (code "85") (name "unconnected-(IC2-SI{slash}WUB-Pad26)") (class "Default")
      (node (ref "IC2") (pin "26") (pinfunction "SI/WUB_26") (pintype "bidirectional"))
    )
    (net (code "86") (name "unconnected-(S2-PadRESERVED)") (class "Default")
      (node (ref "S2") (pin "RESERVED") (pinfunction "RESERVED_RESERVED") (pintype "bidirectional"))
    )
    (net (code "87") (name "unconnected-(U2-Pad3V3)") (class "Default")
      (node (ref "U2") (pin "3V3") (pinfunction "3V3_3V3") (pintype "passive"))
    )
    (net (code "88") (name "unconnected-(U2-PadVB0)") (class "Default")
      (node (ref "U2") (pin "VB0") (pinfunction "VB0_VB0") (pintype "passive"))
    )
  )
)
